# 48V_Converter.net
KiCad netlist of a schematic drawn in Altium Designer
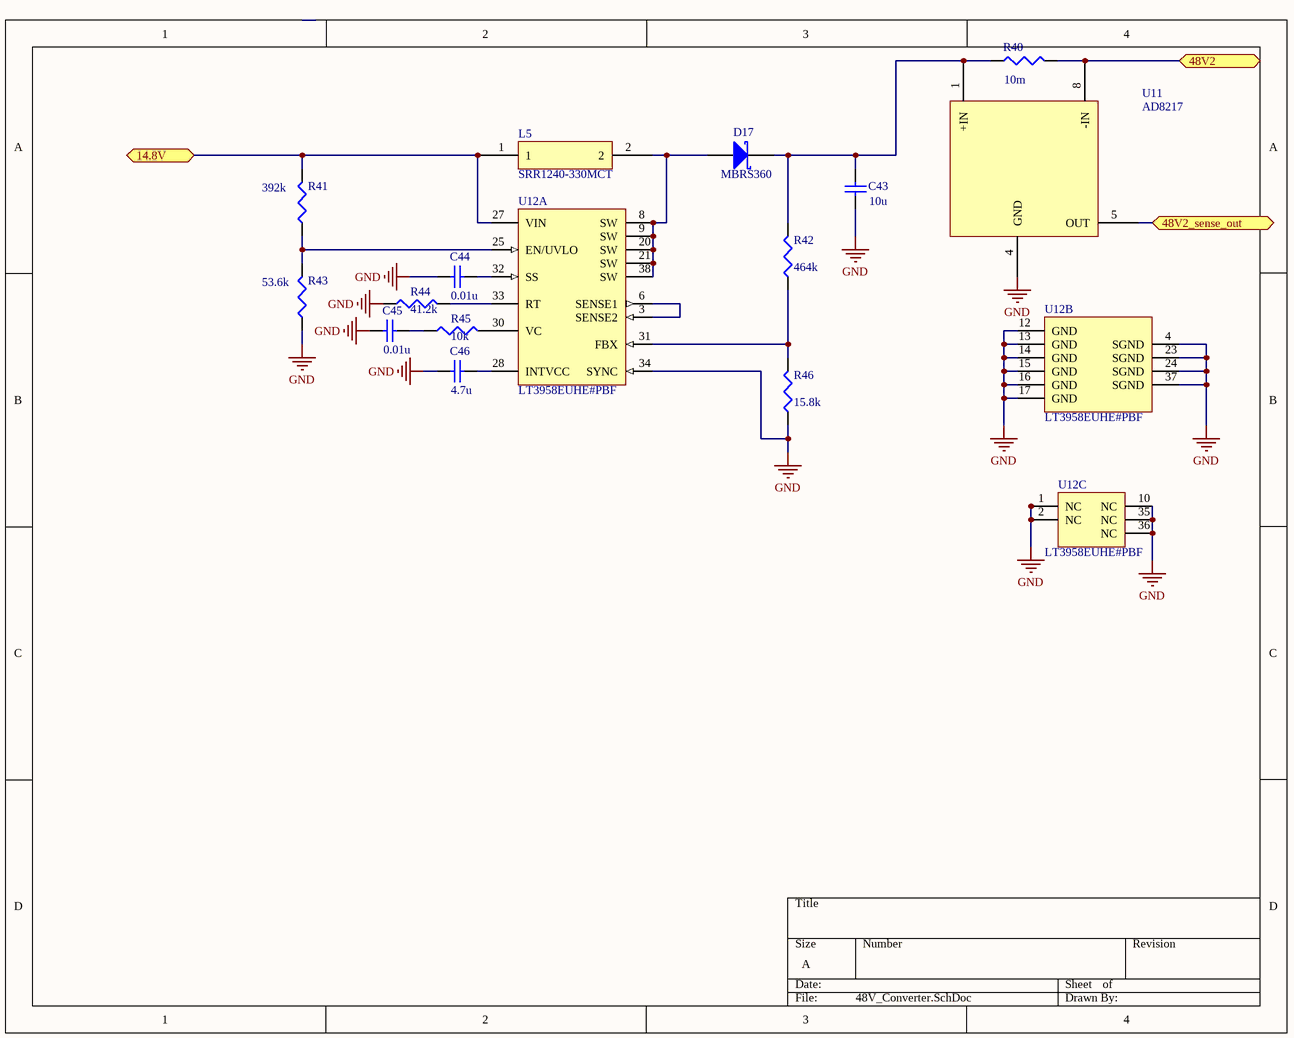
[diagram p0: 48V_Converter.SchDoc]

(export (version "E")
  (design (tool "Eeschema 10.0.6"))
  (components
    (comp (ref "C43")
      (value "10u")
      (footprint "C1206")
      (description "Capacitor (Semiconductor SIM Model)")
      (fields (field (name "Comment") "Cap Semi") (field (name "PUBLISHER") "Altium Limited"))
      (libsource (lib "Miscellaneous Devices") (part "Cap Semi"))
    )
    (comp (ref "C44")
      (value "0.01u")
      (footprint "C1206")
      (description "Capacitor (Semiconductor SIM Model)")
      (fields (field (name "Comment") "Cap Semi") (field (name "PUBLISHER") "Altium Limited"))
      (libsource (lib "Miscellaneous Devices") (part "Cap Semi"))
    )
    (comp (ref "C45")
      (value "0.01u")
      (footprint "C1206")
      (description "Capacitor (Semiconductor SIM Model)")
      (fields (field (name "Comment") "Cap Semi") (field (name "PUBLISHER") "Altium Limited"))
      (libsource (lib "Miscellaneous Devices") (part "Cap Semi"))
    )
    (comp (ref "C46")
      (value "4.7u")
      (footprint "C1206")
      (description "Capacitor (Semiconductor SIM Model)")
      (fields (field (name "Comment") "Cap Semi") (field (name "PUBLISHER") "Altium Limited"))
      (libsource (lib "Miscellaneous Devices") (part "Cap Semi"))
    )
    (comp (ref "D17")
      (value "MBRS360")
      (footprint "SMB")
      (description "Schottky Diode")
      (fields (field (name "PUBLISHER") "Altium Limited"))
      (libsource (lib "Miscellaneous Devices") (part "D Schottky"))
    )
    (comp (ref "L5")
      (value "SRR1240-330MCT")
      (footprint "SRR1240-4R7M")
      (description "Inductor")
      (libsource (lib "Power_Board_Parts_Library") (part "SRR1240-4R7MCT"))
    )
    (comp (ref "R40")
      (value "10m")
      (footprint "J1-0603")
      (description "Resistor")
      (fields (field (name "Comment") "Res3") (field (name "PUBLISHER") "Altium Limited"))
      (libsource (lib "Miscellaneous Devices") (part "Res3"))
    )
    (comp (ref "R41")
      (value "392k")
      (footprint "J1-0603")
      (description "Resistor")
      (fields (field (name "Comment") "Res3") (field (name "PUBLISHER") "Altium Limited"))
      (libsource (lib "Miscellaneous Devices") (part "Res3"))
    )
    (comp (ref "R42")
      (value "464k")
      (footprint "J1-0603")
      (description "Resistor")
      (fields (field (name "Comment") "Res3") (field (name "PUBLISHER") "Altium Limited"))
      (libsource (lib "Miscellaneous Devices") (part "Res3"))
    )
    (comp (ref "R43")
      (value "53.6k")
      (footprint "J1-0603")
      (description "Resistor")
      (fields (field (name "Comment") "Res3") (field (name "PUBLISHER") "Altium Limited"))
      (libsource (lib "Miscellaneous Devices") (part "Res3"))
    )
    (comp (ref "R44")
      (value "41.2k")
      (footprint "J1-0603")
      (description "Resistor")
      (fields (field (name "Comment") "Res3") (field (name "PUBLISHER") "Altium Limited"))
      (libsource (lib "Miscellaneous Devices") (part "Res3"))
    )
    (comp (ref "R45")
      (value "10k")
      (footprint "J1-0603")
      (description "Resistor")
      (fields (field (name "Comment") "Res3") (field (name "PUBLISHER") "Altium Limited"))
      (libsource (lib "Miscellaneous Devices") (part "Res3"))
    )
    (comp (ref "R46")
      (value "15.8k")
      (footprint "J1-0603")
      (description "Resistor")
      (fields (field (name "Comment") "Res3") (field (name "PUBLISHER") "Altium Limited"))
      (libsource (lib "Miscellaneous Devices") (part "Res3"))
    )
    (comp (ref "U11")
      (value "AD8217")
      (footprint "AD8217")
      (description "Current Shunt Moniter")
      (libsource (lib "Integrated_Library") (part "AD8217"))
    )
    (comp (ref "U12")
      (value "LT3958EUHE#PBF")
      (footprint "LT3958")
      (description "LT3958")
      (fields (field (name "MANUFACTURER") "Linear Technology"))
      (libsource (lib "Integrated_Library") (part "LT3958EUHE#PBF"))
    )
  )
  (nets
    (net (code "1") (name "/14.8V") (class "Default")
      (node (ref "L5") (pin "1") (pinfunction "1_1") (pintype "passive"))
      (node (ref "R41") (pin "2") (pinfunction "2_2") (pintype "passive"))
      (node (ref "U12") (pin "27") (pinfunction "VIN_27") (pintype "power_in"))
    )
    (net (code "2") (name "/48V2") (class "Default")
      (node (ref "R40") (pin "2") (pinfunction "2_2") (pintype "passive"))
      (node (ref "U11") (pin "8") (pinfunction "-IN_8") (pintype "passive"))
    )
    (net (code "3") (name "/48V2_sense_out") (class "Default")
      (node (ref "U11") (pin "5") (pinfunction "OUT_5") (pintype "passive"))
    )
    (net (code "4") (name "GND") (class "Default")
      (node (ref "C43") (pin "1") (pinfunction "1_1") (pintype "passive"))
      (node (ref "C44") (pin "1") (pinfunction "1_1") (pintype "passive"))
      (node (ref "C45") (pin "1") (pinfunction "1_1") (pintype "passive"))
      (node (ref "C46") (pin "1") (pinfunction "1_1") (pintype "passive"))
      (node (ref "R43") (pin "1") (pinfunction "1_1") (pintype "passive"))
      (node (ref "R44") (pin "1") (pinfunction "1_1") (pintype "passive"))
      (node (ref "R46") (pin "1") (pinfunction "1_1") (pintype "passive"))
      (node (ref "U11") (pin "4") (pinfunction "GND_4") (pintype "passive"))
      (node (ref "U12") (pin "1") (pinfunction "NC_1") (pintype "passive"))
      (node (ref "U12") (pin "10") (pinfunction "NC_10") (pintype "passive"))
      (node (ref "U12") (pin "12") (pinfunction "GND_12") (pintype "power_in"))
      (node (ref "U12") (pin "13") (pinfunction "GND_13") (pintype "power_in"))
      (node (ref "U12") (pin "14") (pinfunction "GND_14") (pintype "power_in"))
      (node (ref "U12") (pin "15") (pinfunction "GND_15") (pintype "power_in"))
      (node (ref "U12") (pin "16") (pinfunction "GND_16") (pintype "power_in"))
      (node (ref "U12") (pin "17") (pinfunction "GND_17") (pintype "power_in"))
      (node (ref "U12") (pin "2") (pinfunction "NC_2") (pintype "passive"))
      (node (ref "U12") (pin "23") (pinfunction "SGND_23") (pintype "power_in"))
      (node (ref "U12") (pin "24") (pinfunction "SGND_24") (pintype "power_in"))
      (node (ref "U12") (pin "34") (pinfunction "SYNC_34") (pintype "input"))
      (node (ref "U12") (pin "35") (pinfunction "NC_35") (pintype "passive"))
      (node (ref "U12") (pin "36") (pinfunction "NC_36") (pintype "passive"))
      (node (ref "U12") (pin "37") (pinfunction "SGND_37") (pintype "power_in"))
      (node (ref "U12") (pin "4") (pinfunction "SGND_4") (pintype "power_in"))
    )
    (net (code "5") (name "Net-(C45-Pad2)") (class "Default")
      (node (ref "C45") (pin "2") (pinfunction "2_2") (pintype "passive"))
      (node (ref "R45") (pin "1") (pinfunction "1_1") (pintype "passive"))
    )
    (net (code "6") (name "Net-(D17-A)") (class "Default")
      (node (ref "D17") (pin "1") (pinfunction "A_1") (pintype "passive"))
      (node (ref "L5") (pin "2") (pinfunction "2_2") (pintype "passive"))
      (node (ref "U12") (pin "20") (pinfunction "SW_20") (pintype "power_in"))
      (node (ref "U12") (pin "21") (pinfunction "SW_21") (pintype "power_in"))
      (node (ref "U12") (pin "38") (pinfunction "SW_38") (pintype "power_in"))
      (node (ref "U12") (pin "8") (pinfunction "SW_8") (pintype "power_in"))
      (node (ref "U12") (pin "9") (pinfunction "SW_9") (pintype "power_in"))
    )
    (net (code "7") (name "Net-(D17-K)") (class "Default")
      (node (ref "C43") (pin "2") (pinfunction "2_2") (pintype "passive"))
      (node (ref "D17") (pin "2") (pinfunction "K_2") (pintype "passive"))
      (node (ref "R40") (pin "1") (pinfunction "1_1") (pintype "passive"))
      (node (ref "R42") (pin "2") (pinfunction "2_2") (pintype "passive"))
      (node (ref "U11") (pin "1") (pinfunction "+IN_1") (pintype "passive"))
    )
    (net (code "8") (name "Net-(U12A-EN{slash}UVLO)") (class "Default")
      (node (ref "R41") (pin "1") (pinfunction "1_1") (pintype "passive"))
      (node (ref "R43") (pin "2") (pinfunction "2_2") (pintype "passive"))
      (node (ref "U12") (pin "25") (pinfunction "EN/UVLO_25") (pintype "input"))
    )
    (net (code "9") (name "Net-(U12A-FBX)") (class "Default")
      (node (ref "R42") (pin "1") (pinfunction "1_1") (pintype "passive"))
      (node (ref "R46") (pin "2") (pinfunction "2_2") (pintype "passive"))
      (node (ref "U12") (pin "31") (pinfunction "FBX_31") (pintype "input"))
    )
    (net (code "10") (name "Net-(U12A-INTVCC)") (class "Default")
      (node (ref "C46") (pin "2") (pinfunction "2_2") (pintype "passive"))
      (node (ref "U12") (pin "28") (pinfunction "INTVCC_28") (pintype "power_in"))
    )
    (net (code "11") (name "Net-(U12A-RT)") (class "Default")
      (node (ref "R44") (pin "2") (pinfunction "2_2") (pintype "passive"))
      (node (ref "U12") (pin "33") (pinfunction "RT_33") (pintype "passive"))
    )
    (net (code "12") (name "Net-(U12A-SENSE1)") (class "Default")
      (node (ref "U12") (pin "3") (pinfunction "SENSE2_3") (pintype "input"))
      (node (ref "U12") (pin "6") (pinfunction "SENSE1_6") (pintype "output"))
    )
    (net (code "13") (name "Net-(U12A-SS)") (class "Default")
      (node (ref "C44") (pin "2") (pinfunction "2_2") (pintype "passive"))
      (node (ref "U12") (pin "32") (pinfunction "SS_32") (pintype "input"))
    )
    (net (code "14") (name "Net-(U12A-VC)") (class "Default")
      (node (ref "R45") (pin "2") (pinfunction "2_2") (pintype "passive"))
      (node (ref "U12") (pin "30") (pinfunction "VC_30") (pintype "passive"))
    )
  )
)
